# piano_pcb.net
KiCad netlist of a schematic drawn in EAGLE
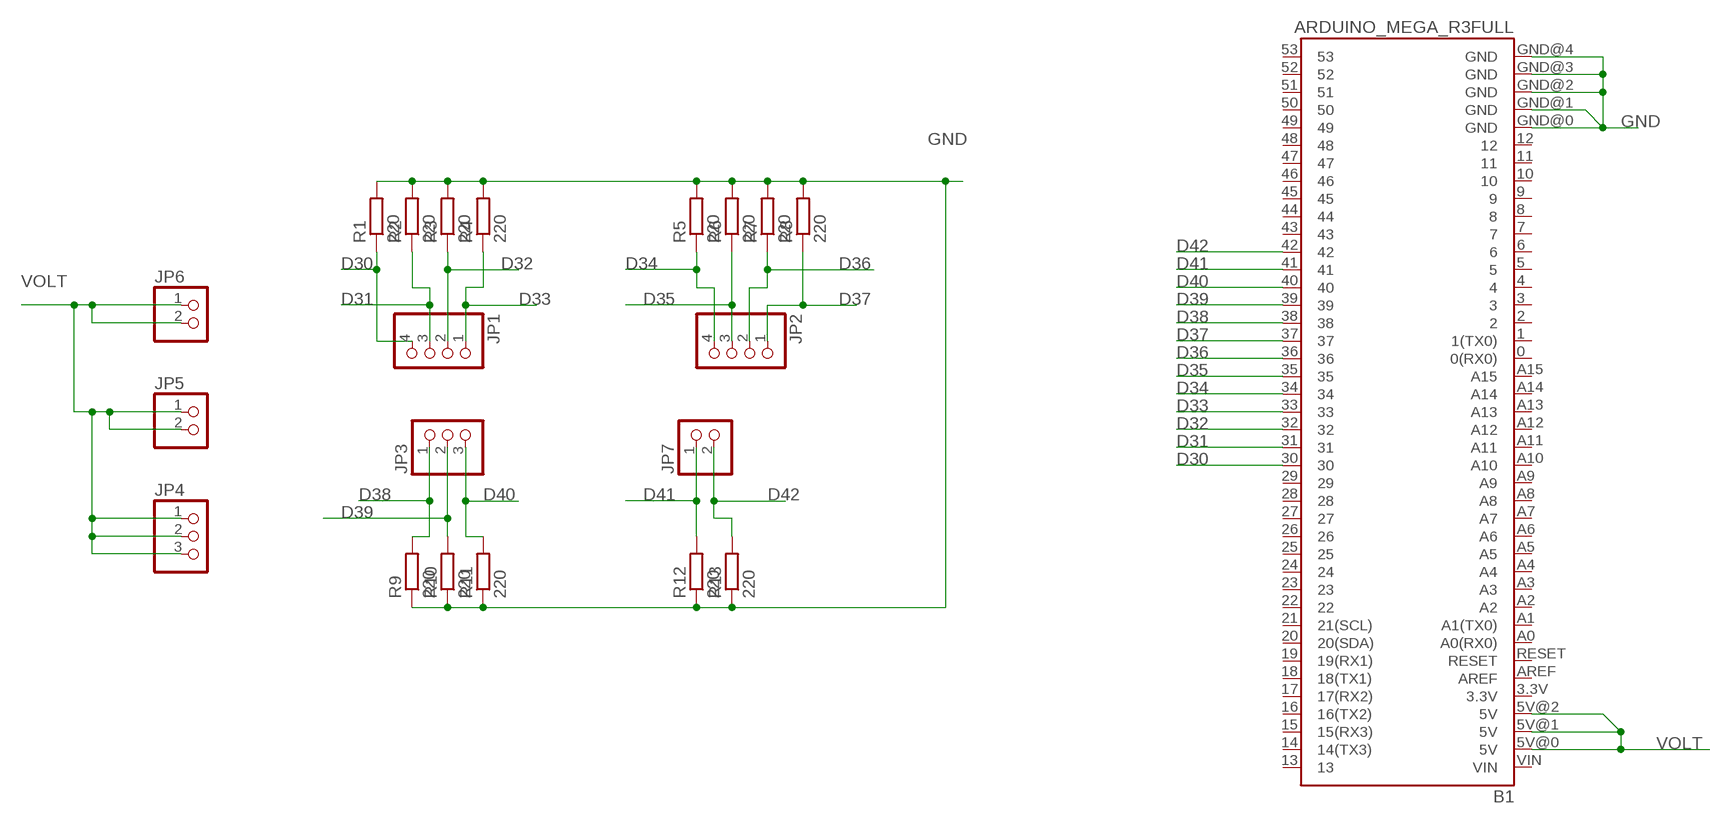
[diagram p0: schematic, sheet 1]

(export (version "E")
  (design (tool "Eeschema 10.0.6"))
  (components
    (comp (ref "B1")
      (value "ARDUINO_MEGA_R3FULL")
      (footprint "eagle-import:ARDUINO_MEGA")
      (libsource (lib "eagle-import") (part "ARDUINO_MEGA_R3FULL"))
    )
    (comp (ref "JP1")
      (value "PINHD-1X4")
      (footprint "eagle-import:1X04")
      (libsource (lib "eagle-import") (part "PINHD-1X4"))
    )
    (comp (ref "JP2")
      (value "PINHD-1X4")
      (footprint "eagle-import:1X04")
      (libsource (lib "eagle-import") (part "PINHD-1X4"))
    )
    (comp (ref "JP3")
      (value "PINHD-1X3")
      (footprint "eagle-import:1X03")
      (libsource (lib "eagle-import") (part "PINHD-1X3"))
    )
    (comp (ref "JP4")
      (value "PINHD-1X3")
      (footprint "eagle-import:1X03")
      (libsource (lib "eagle-import") (part "PINHD-1X3"))
    )
    (comp (ref "JP5")
      (value "PINHD-1X2")
      (footprint "eagle-import:1X02")
      (libsource (lib "eagle-import") (part "PINHD-1X2"))
    )
    (comp (ref "JP6")
      (value "PINHD-1X2")
      (footprint "eagle-import:1X02")
      (libsource (lib "eagle-import") (part "PINHD-1X2"))
    )
    (comp (ref "JP7")
      (value "PINHD-1X2")
      (footprint "eagle-import:1X02")
      (libsource (lib "eagle-import") (part "PINHD-1X2"))
    )
    (comp (ref "R1")
      (value "220")
      (footprint "eagle-import:0204_5")
      (libsource (lib "eagle-import") (part "R-EU_0204/5"))
    )
    (comp (ref "R2")
      (value "220")
      (footprint "eagle-import:0204_5")
      (libsource (lib "eagle-import") (part "R-EU_0204/5"))
    )
    (comp (ref "R3")
      (value "220")
      (footprint "eagle-import:0204_5")
      (libsource (lib "eagle-import") (part "R-EU_0204/5"))
    )
    (comp (ref "R4")
      (value "220")
      (footprint "eagle-import:0204_5")
      (libsource (lib "eagle-import") (part "R-EU_0204/5"))
    )
    (comp (ref "R5")
      (value "220")
      (footprint "eagle-import:0204_5")
      (libsource (lib "eagle-import") (part "R-EU_0204/5"))
    )
    (comp (ref "R6")
      (value "220")
      (footprint "eagle-import:0204_5")
      (libsource (lib "eagle-import") (part "R-EU_0204/5"))
    )
    (comp (ref "R7")
      (value "220")
      (footprint "eagle-import:0204_5")
      (libsource (lib "eagle-import") (part "R-EU_0204/5"))
    )
    (comp (ref "R8")
      (value "220")
      (footprint "eagle-import:0204_5")
      (libsource (lib "eagle-import") (part "R-EU_0204/5"))
    )
    (comp (ref "R9")
      (value "220")
      (footprint "eagle-import:0204_5")
      (libsource (lib "eagle-import") (part "R-EU_0204/5"))
    )
    (comp (ref "R10")
      (value "220")
      (footprint "eagle-import:0204_5")
      (libsource (lib "eagle-import") (part "R-EU_0204/5"))
    )
    (comp (ref "R11")
      (value "220")
      (footprint "eagle-import:0204_5")
      (libsource (lib "eagle-import") (part "R-EU_0204/5"))
    )
    (comp (ref "R12")
      (value "220")
      (footprint "eagle-import:0204_5")
      (libsource (lib "eagle-import") (part "R-EU_0204/5"))
    )
    (comp (ref "R13")
      (value "220")
      (footprint "eagle-import:0204_5")
      (libsource (lib "eagle-import") (part "R-EU_0204/5"))
    )
  )
  (nets
    (net (code "1") (name "/D30") (class "Default")
      (node (ref "B1") (pin "30") (pinfunction "30_30") (pintype "bidirectional"))
      (node (ref "JP1") (pin "4") (pinfunction "4_4") (pintype "passive"))
      (node (ref "R1") (pin "1") (pinfunction "1_1") (pintype "passive"))
    )
    (net (code "2") (name "/D31") (class "Default")
      (node (ref "B1") (pin "31") (pinfunction "31_31") (pintype "bidirectional"))
      (node (ref "JP1") (pin "3") (pinfunction "3_3") (pintype "passive"))
      (node (ref "R2") (pin "1") (pinfunction "1_1") (pintype "passive"))
    )
    (net (code "3") (name "/D32") (class "Default")
      (node (ref "B1") (pin "32") (pinfunction "32_32") (pintype "bidirectional"))
      (node (ref "JP1") (pin "2") (pinfunction "2_2") (pintype "passive"))
      (node (ref "R3") (pin "1") (pinfunction "1_1") (pintype "passive"))
    )
    (net (code "4") (name "/D33") (class "Default")
      (node (ref "B1") (pin "33") (pinfunction "33_33") (pintype "bidirectional"))
      (node (ref "JP1") (pin "1") (pinfunction "1_1") (pintype "passive"))
      (node (ref "R4") (pin "1") (pinfunction "1_1") (pintype "passive"))
    )
    (net (code "5") (name "/D34") (class "Default")
      (node (ref "B1") (pin "34") (pinfunction "34_34") (pintype "bidirectional"))
      (node (ref "JP2") (pin "4") (pinfunction "4_4") (pintype "passive"))
      (node (ref "R5") (pin "1") (pinfunction "1_1") (pintype "passive"))
    )
    (net (code "6") (name "/D35") (class "Default")
      (node (ref "B1") (pin "35") (pinfunction "35_35") (pintype "bidirectional"))
      (node (ref "JP2") (pin "3") (pinfunction "3_3") (pintype "passive"))
      (node (ref "R6") (pin "1") (pinfunction "1_1") (pintype "passive"))
    )
    (net (code "7") (name "/D36") (class "Default")
      (node (ref "B1") (pin "36") (pinfunction "36_36") (pintype "bidirectional"))
      (node (ref "JP2") (pin "2") (pinfunction "2_2") (pintype "passive"))
      (node (ref "R7") (pin "1") (pinfunction "1_1") (pintype "passive"))
    )
    (net (code "8") (name "/D37") (class "Default")
      (node (ref "B1") (pin "37") (pinfunction "37_37") (pintype "bidirectional"))
      (node (ref "JP2") (pin "1") (pinfunction "1_1") (pintype "passive"))
      (node (ref "R8") (pin "1") (pinfunction "1_1") (pintype "passive"))
    )
    (net (code "9") (name "/D38") (class "Default")
      (node (ref "B1") (pin "38") (pinfunction "38_38") (pintype "bidirectional"))
      (node (ref "JP3") (pin "1") (pinfunction "1_1") (pintype "passive"))
      (node (ref "R9") (pin "2") (pinfunction "2_2") (pintype "passive"))
    )
    (net (code "10") (name "/D39") (class "Default")
      (node (ref "B1") (pin "39") (pinfunction "39_39") (pintype "bidirectional"))
      (node (ref "JP3") (pin "2") (pinfunction "2_2") (pintype "passive"))
      (node (ref "R10") (pin "2") (pinfunction "2_2") (pintype "passive"))
    )
    (net (code "11") (name "/D40") (class "Default")
      (node (ref "B1") (pin "40") (pinfunction "40_40") (pintype "bidirectional"))
      (node (ref "JP3") (pin "3") (pinfunction "3_3") (pintype "passive"))
      (node (ref "R11") (pin "2") (pinfunction "2_2") (pintype "passive"))
    )
    (net (code "12") (name "/D41") (class "Default")
      (node (ref "B1") (pin "41") (pinfunction "41_41") (pintype "bidirectional"))
      (node (ref "JP7") (pin "1") (pinfunction "1_1") (pintype "passive"))
      (node (ref "R12") (pin "2") (pinfunction "2_2") (pintype "passive"))
    )
    (net (code "13") (name "/D42") (class "Default")
      (node (ref "B1") (pin "42") (pinfunction "42_42") (pintype "bidirectional"))
      (node (ref "JP7") (pin "2") (pinfunction "2_2") (pintype "passive"))
      (node (ref "R13") (pin "2") (pinfunction "2_2") (pintype "passive"))
    )
    (net (code "14") (name "/GND") (class "Default")
      (node (ref "B1") (pin "GND@0") (pinfunction "GND_GND@0") (pintype "bidirectional"))
      (node (ref "B1") (pin "GND@1") (pinfunction "GND_GND@1") (pintype "bidirectional"))
      (node (ref "B1") (pin "GND@2") (pinfunction "GND_GND@2") (pintype "bidirectional"))
      (node (ref "B1") (pin "GND@3") (pinfunction "GND_GND@3") (pintype "bidirectional"))
      (node (ref "B1") (pin "GND@4") (pinfunction "GND_GND@4") (pintype "bidirectional"))
      (node (ref "R1") (pin "2") (pinfunction "2_2") (pintype "passive"))
      (node (ref "R10") (pin "1") (pinfunction "1_1") (pintype "passive"))
      (node (ref "R11") (pin "1") (pinfunction "1_1") (pintype "passive"))
      (node (ref "R12") (pin "1") (pinfunction "1_1") (pintype "passive"))
      (node (ref "R13") (pin "1") (pinfunction "1_1") (pintype "passive"))
      (node (ref "R2") (pin "2") (pinfunction "2_2") (pintype "passive"))
      (node (ref "R3") (pin "2") (pinfunction "2_2") (pintype "passive"))
      (node (ref "R4") (pin "2") (pinfunction "2_2") (pintype "passive"))
      (node (ref "R5") (pin "2") (pinfunction "2_2") (pintype "passive"))
      (node (ref "R6") (pin "2") (pinfunction "2_2") (pintype "passive"))
      (node (ref "R7") (pin "2") (pinfunction "2_2") (pintype "passive"))
      (node (ref "R8") (pin "2") (pinfunction "2_2") (pintype "passive"))
      (node (ref "R9") (pin "1") (pinfunction "1_1") (pintype "passive"))
    )
    (net (code "15") (name "/VOLT") (class "Default")
      (node (ref "B1") (pin "5V@0") (pinfunction "5V_5V@0") (pintype "bidirectional"))
      (node (ref "B1") (pin "5V@1") (pinfunction "5V_5V@1") (pintype "bidirectional"))
      (node (ref "B1") (pin "5V@2") (pinfunction "5V_5V@2") (pintype "bidirectional"))
      (node (ref "JP4") (pin "1") (pinfunction "1_1") (pintype "passive"))
      (node (ref "JP4") (pin "2") (pinfunction "2_2") (pintype "passive"))
      (node (ref "JP4") (pin "3") (pinfunction "3_3") (pintype "passive"))
      (node (ref "JP5") (pin "1") (pinfunction "1_1") (pintype "passive"))
      (node (ref "JP5") (pin "2") (pinfunction "2_2") (pintype "passive"))
      (node (ref "JP6") (pin "1") (pinfunction "1_1") (pintype "passive"))
      (node (ref "JP6") (pin "2") (pinfunction "2_2") (pintype "passive"))
    )
    (net (code "16") (name "unconnected-(B1-0(RX0)-Pad0)") (class "Default")
      (node (ref "B1") (pin "0") (pinfunction "0(RX0)_0") (pintype "bidirectional"))
    )
    (net (code "17") (name "unconnected-(B1-1(TX0)-Pad1)") (class "Default")
      (node (ref "B1") (pin "1") (pinfunction "1(TX0)_1") (pintype "bidirectional"))
    )
    (net (code "18") (name "unconnected-(B1-14(TX3)-Pad14)") (class "Default")
      (node (ref "B1") (pin "14") (pinfunction "14(TX3)_14") (pintype "bidirectional"))
    )
    (net (code "19") (name "unconnected-(B1-15(RX3)-Pad15)") (class "Default")
      (node (ref "B1") (pin "15") (pinfunction "15(RX3)_15") (pintype "bidirectional"))
    )
    (net (code "20") (name "unconnected-(B1-16(TX2)-Pad16)") (class "Default")
      (node (ref "B1") (pin "16") (pinfunction "16(TX2)_16") (pintype "bidirectional"))
    )
    (net (code "21") (name "unconnected-(B1-17(RX2)-Pad17)") (class "Default")
      (node (ref "B1") (pin "17") (pinfunction "17(RX2)_17") (pintype "bidirectional"))
    )
    (net (code "22") (name "unconnected-(B1-18(TX1)-Pad18)") (class "Default")
      (node (ref "B1") (pin "18") (pinfunction "18(TX1)_18") (pintype "bidirectional"))
    )
    (net (code "23") (name "unconnected-(B1-19(RX1)-Pad19)") (class "Default")
      (node (ref "B1") (pin "19") (pinfunction "19(RX1)_19") (pintype "bidirectional"))
    )
    (net (code "24") (name "unconnected-(B1-20(SDA)-Pad20)") (class "Default")
      (node (ref "B1") (pin "20") (pinfunction "20(SDA)_20") (pintype "bidirectional"))
    )
    (net (code "25") (name "unconnected-(B1-21(SCL)-Pad21)") (class "Default")
      (node (ref "B1") (pin "21") (pinfunction "21(SCL)_21") (pintype "bidirectional"))
    )
    (net (code "26") (name "unconnected-(B1-A0(RX0)-PadA0)") (class "Default")
      (node (ref "B1") (pin "A0") (pinfunction "A0(RX0)_A0") (pintype "bidirectional"))
    )
    (net (code "27") (name "unconnected-(B1-A1(TX0)-PadA1)") (class "Default")
      (node (ref "B1") (pin "A1") (pinfunction "A1(TX0)_A1") (pintype "bidirectional"))
    )
    (net (code "28") (name "unconnected-(B1-Pad2)") (class "Default")
      (node (ref "B1") (pin "2") (pinfunction "2_2") (pintype "bidirectional"))
    )
    (net (code "29") (name "unconnected-(B1-Pad3)") (class "Default")
      (node (ref "B1") (pin "3") (pinfunction "3_3") (pintype "bidirectional"))
    )
    (net (code "30") (name "unconnected-(B1-Pad3.3V)") (class "Default")
      (node (ref "B1") (pin "3.3V") (pinfunction "3.3V_3.3V") (pintype "bidirectional"))
    )
    (net (code "31") (name "unconnected-(B1-Pad4)") (class "Default")
      (node (ref "B1") (pin "4") (pinfunction "4_4") (pintype "bidirectional"))
    )
    (net (code "32") (name "unconnected-(B1-Pad5)") (class "Default")
      (node (ref "B1") (pin "5") (pinfunction "5_5") (pintype "bidirectional"))
    )
    (net (code "33") (name "unconnected-(B1-Pad6)") (class "Default")
      (node (ref "B1") (pin "6") (pinfunction "6_6") (pintype "bidirectional"))
    )
    (net (code "34") (name "unconnected-(B1-Pad7)") (class "Default")
      (node (ref "B1") (pin "7") (pinfunction "7_7") (pintype "bidirectional"))
    )
    (net (code "35") (name "unconnected-(B1-Pad8)") (class "Default")
      (node (ref "B1") (pin "8") (pinfunction "8_8") (pintype "bidirectional"))
    )
    (net (code "36") (name "unconnected-(B1-Pad9)") (class "Default")
      (node (ref "B1") (pin "9") (pinfunction "9_9") (pintype "bidirectional"))
    )
    (net (code "37") (name "unconnected-(B1-Pad10)") (class "Default")
      (node (ref "B1") (pin "10") (pinfunction "10_10") (pintype "bidirectional"))
    )
    (net (code "38") (name "unconnected-(B1-Pad11)") (class "Default")
      (node (ref "B1") (pin "11") (pinfunction "11_11") (pintype "bidirectional"))
    )
    (net (code "39") (name "unconnected-(B1-Pad12)") (class "Default")
      (node (ref "B1") (pin "12") (pinfunction "12_12") (pintype "bidirectional"))
    )
    (net (code "40") (name "unconnected-(B1-Pad13)") (class "Default")
      (node (ref "B1") (pin "13") (pinfunction "13_13") (pintype "bidirectional"))
    )
    (net (code "41") (name "unconnected-(B1-Pad22)") (class "Default")
      (node (ref "B1") (pin "22") (pinfunction "22_22") (pintype "bidirectional"))
    )
    (net (code "42") (name "unconnected-(B1-Pad23)") (class "Default")
      (node (ref "B1") (pin "23") (pinfunction "23_23") (pintype "bidirectional"))
    )
    (net (code "43") (name "unconnected-(B1-Pad24)") (class "Default")
      (node (ref "B1") (pin "24") (pinfunction "24_24") (pintype "bidirectional"))
    )
    (net (code "44") (name "unconnected-(B1-Pad25)") (class "Default")
      (node (ref "B1") (pin "25") (pinfunction "25_25") (pintype "bidirectional"))
    )
    (net (code "45") (name "unconnected-(B1-Pad26)") (class "Default")
      (node (ref "B1") (pin "26") (pinfunction "26_26") (pintype "bidirectional"))
    )
    (net (code "46") (name "unconnected-(B1-Pad27)") (class "Default")
      (node (ref "B1") (pin "27") (pinfunction "27_27") (pintype "bidirectional"))
    )
    (net (code "47") (name "unconnected-(B1-Pad28)") (class "Default")
      (node (ref "B1") (pin "28") (pinfunction "28_28") (pintype "bidirectional"))
    )
    (net (code "48") (name "unconnected-(B1-Pad29)") (class "Default")
      (node (ref "B1") (pin "29") (pinfunction "29_29") (pintype "bidirectional"))
    )
    (net (code "49") (name "unconnected-(B1-Pad43)") (class "Default")
      (node (ref "B1") (pin "43") (pinfunction "43_43") (pintype "bidirectional"))
    )
    (net (code "50") (name "unconnected-(B1-Pad44)") (class "Default")
      (node (ref "B1") (pin "44") (pinfunction "44_44") (pintype "bidirectional"))
    )
    (net (code "51") (name "unconnected-(B1-Pad45)") (class "Default")
      (node (ref "B1") (pin "45") (pinfunction "45_45") (pintype "bidirectional"))
    )
    (net (code "52") (name "unconnected-(B1-Pad46)") (class "Default")
      (node (ref "B1") (pin "46") (pinfunction "46_46") (pintype "bidirectional"))
    )
    (net (code "53") (name "unconnected-(B1-Pad47)") (class "Default")
      (node (ref "B1") (pin "47") (pinfunction "47_47") (pintype "bidirectional"))
    )
    (net (code "54") (name "unconnected-(B1-Pad48)") (class "Default")
      (node (ref "B1") (pin "48") (pinfunction "48_48") (pintype "bidirectional"))
    )
    (net (code "55") (name "unconnected-(B1-Pad49)") (class "Default")
      (node (ref "B1") (pin "49") (pinfunction "49_49") (pintype "bidirectional"))
    )
    (net (code "56") (name "unconnected-(B1-Pad50)") (class "Default")
      (node (ref "B1") (pin "50") (pinfunction "50_50") (pintype "bidirectional"))
    )
    (net (code "57") (name "unconnected-(B1-Pad51)") (class "Default")
      (node (ref "B1") (pin "51") (pinfunction "51_51") (pintype "bidirectional"))
    )
    (net (code "58") (name "unconnected-(B1-Pad52)") (class "Default")
      (node (ref "B1") (pin "52") (pinfunction "52_52") (pintype "bidirectional"))
    )
    (net (code "59") (name "unconnected-(B1-Pad53)") (class "Default")
      (node (ref "B1") (pin "53") (pinfunction "53_53") (pintype "bidirectional"))
    )
    (net (code "60") (name "unconnected-(B1-PadA2)") (class "Default")
      (node (ref "B1") (pin "A2") (pinfunction "A2_A2") (pintype "bidirectional"))
    )
    (net (code "61") (name "unconnected-(B1-PadA3)") (class "Default")
      (node (ref "B1") (pin "A3") (pinfunction "A3_A3") (pintype "bidirectional"))
    )
    (net (code "62") (name "unconnected-(B1-PadA4)") (class "Default")
      (node (ref "B1") (pin "A4") (pinfunction "A4_A4") (pintype "bidirectional"))
    )
    (net (code "63") (name "unconnected-(B1-PadA5)") (class "Default")
      (node (ref "B1") (pin "A5") (pinfunction "A5_A5") (pintype "bidirectional"))
    )
    (net (code "64") (name "unconnected-(B1-PadA6)") (class "Default")
      (node (ref "B1") (pin "A6") (pinfunction "A6_A6") (pintype "bidirectional"))
    )
    (net (code "65") (name "unconnected-(B1-PadA7)") (class "Default")
      (node (ref "B1") (pin "A7") (pinfunction "A7_A7") (pintype "bidirectional"))
    )
    (net (code "66") (name "unconnected-(B1-PadA8)") (class "Default")
      (node (ref "B1") (pin "A8") (pinfunction "A8_A8") (pintype "bidirectional"))
    )
    (net (code "67") (name "unconnected-(B1-PadA9)") (class "Default")
      (node (ref "B1") (pin "A9") (pinfunction "A9_A9") (pintype "bidirectional"))
    )
    (net (code "68") (name "unconnected-(B1-PadA10)") (class "Default")
      (node (ref "B1") (pin "A10") (pinfunction "A10_A10") (pintype "bidirectional"))
    )
    (net (code "69") (name "unconnected-(B1-PadA11)") (class "Default")
      (node (ref "B1") (pin "A11") (pinfunction "A11_A11") (pintype "bidirectional"))
    )
    (net (code "70") (name "unconnected-(B1-PadA12)") (class "Default")
      (node (ref "B1") (pin "A12") (pinfunction "A12_A12") (pintype "bidirectional"))
    )
    (net (code "71") (name "unconnected-(B1-PadA13)") (class "Default")
      (node (ref "B1") (pin "A13") (pinfunction "A13_A13") (pintype "bidirectional"))
    )
    (net (code "72") (name "unconnected-(B1-PadA14)") (class "Default")
      (node (ref "B1") (pin "A14") (pinfunction "A14_A14") (pintype "bidirectional"))
    )
    (net (code "73") (name "unconnected-(B1-PadA15)") (class "Default")
      (node (ref "B1") (pin "A15") (pinfunction "A15_A15") (pintype "bidirectional"))
    )
    (net (code "74") (name "unconnected-(B1-PadAREF)") (class "Default")
      (node (ref "B1") (pin "AREF") (pinfunction "AREF_AREF") (pintype "bidirectional"))
    )
    (net (code "75") (name "unconnected-(B1-PadRESET)") (class "Default")
      (node (ref "B1") (pin "RESET") (pinfunction "RESET_RESET") (pintype "bidirectional"))
    )
    (net (code "76") (name "unconnected-(B1-PadVIN)") (class "Default")
      (node (ref "B1") (pin "VIN") (pinfunction "VIN_VIN") (pintype "bidirectional"))
    )
  )
)
